# SENSORS.net
KiCad netlist of a schematic drawn in Altium Designer
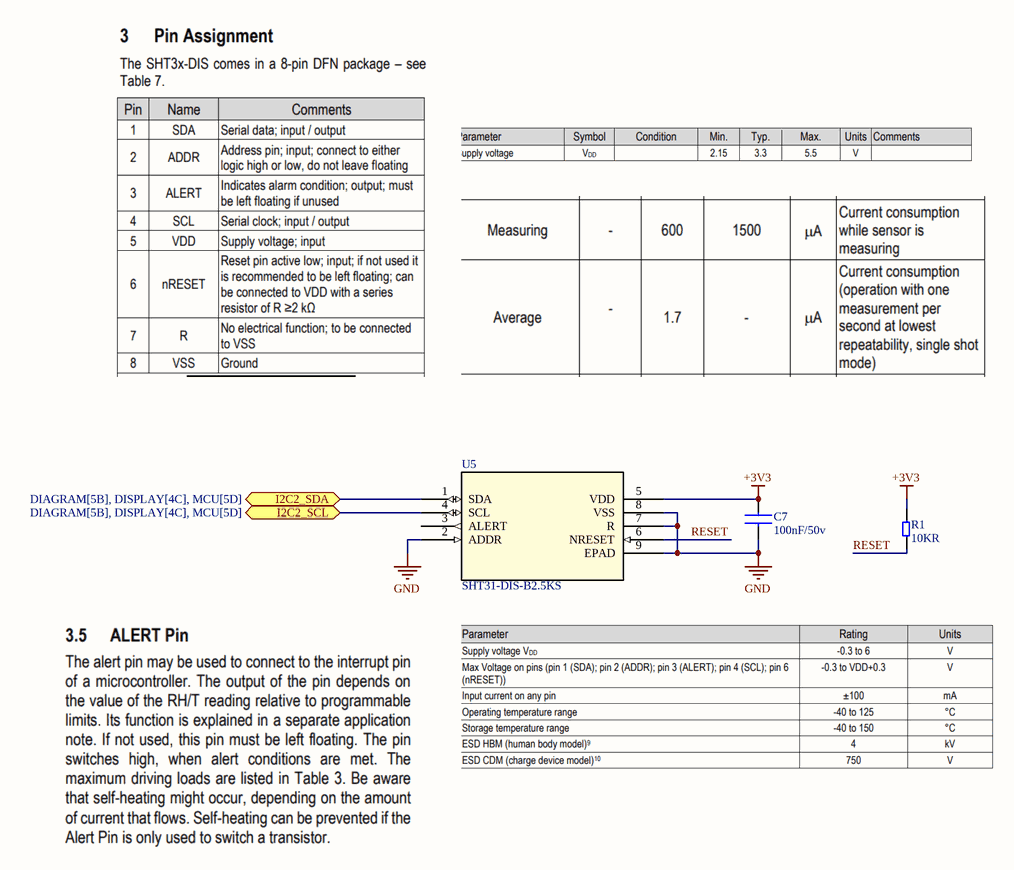
[diagram p0: SENSORS.SchDoc]

(export (version "E")
  (design (tool "Eeschema 10.0.6"))
  (components
    (comp (ref "C7") (value "100nF/50v") (footprint "CAP-CER-0805") (libsource (lib "ID") (part "CAP-CER")))
    (comp (ref "R1")
      (value "10KR")
      (footprint "RES-SMD-0805")
      (description "Điện Trở 10 KOhm 0805 1%")
      (libsource (lib "Database_Libs1") (part "RES_SMD"))
    )
    (comp (ref "U5")
      (value "SHT31-DIS-B2.5KS")
      (footprint "SHT31-DIS-B2.5KS_U_SHT3_SEN")
      (description "Humidity, Temperature 0 ~ 100% RH I2C ±2% RH 8 s Surface Mount")
      (fields
        (field (name "MFR# #") "SHT31-DIS-B2.5KS")
        (field (name "COPYRIGHT") "Copyright (C) 2025 Ultra Librarian. All rights reserved.")
      )
      (libsource (lib "Database_Libs1") (part "SHT31-DIS-B2.5KS"))
    )
  )
  (nets
    (net (code "1") (name "+3V3") (class "Default")
      (node (ref "C7") (pin "2") (pinfunction "2_2") (pintype "passive"))
      (node (ref "R1") (pin "2") (pinfunction "2_2") (pintype "passive"))
      (node (ref "U5") (pin "5") (pinfunction "VDD_5") (pintype "power_in"))
    )
    (net (code "2") (name "/I2C2_SCL") (class "Default")
      (node (ref "U5") (pin "4") (pinfunction "SCL_4") (pintype "bidirectional"))
    )
    (net (code "3") (name "/I2C2_SDA") (class "Default")
      (node (ref "U5") (pin "1") (pinfunction "SDA_1") (pintype "bidirectional"))
    )
    (net (code "4") (name "/RESET") (class "Default")
      (node (ref "R1") (pin "1") (pinfunction "1_1") (pintype "passive"))
      (node (ref "U5") (pin "6") (pinfunction "NRESET_6") (pintype "input"))
    )
    (net (code "5") (name "GND") (class "Default")
      (node (ref "C7") (pin "1") (pinfunction "1_1") (pintype "passive"))
      (node (ref "U5") (pin "2") (pinfunction "ADDR_2") (pintype "input"))
      (node (ref "U5") (pin "7") (pinfunction "R_7") (pintype "power_in"))
      (node (ref "U5") (pin "8") (pinfunction "VSS_8") (pintype "power_in"))
      (node (ref "U5") (pin "9") (pinfunction "EPAD_9") (pintype "power_in"))
    )
    (net (code "6") (name "unconnected-(U5-ALERT-Pad3)") (class "Default")
      (node (ref "U5") (pin "3") (pinfunction "ALERT_3") (pintype "output"))
    )
  )
)
